# spectrum_8kHz_64Hz.net
KiCad netlist of a schematic drawn in Altium Designer
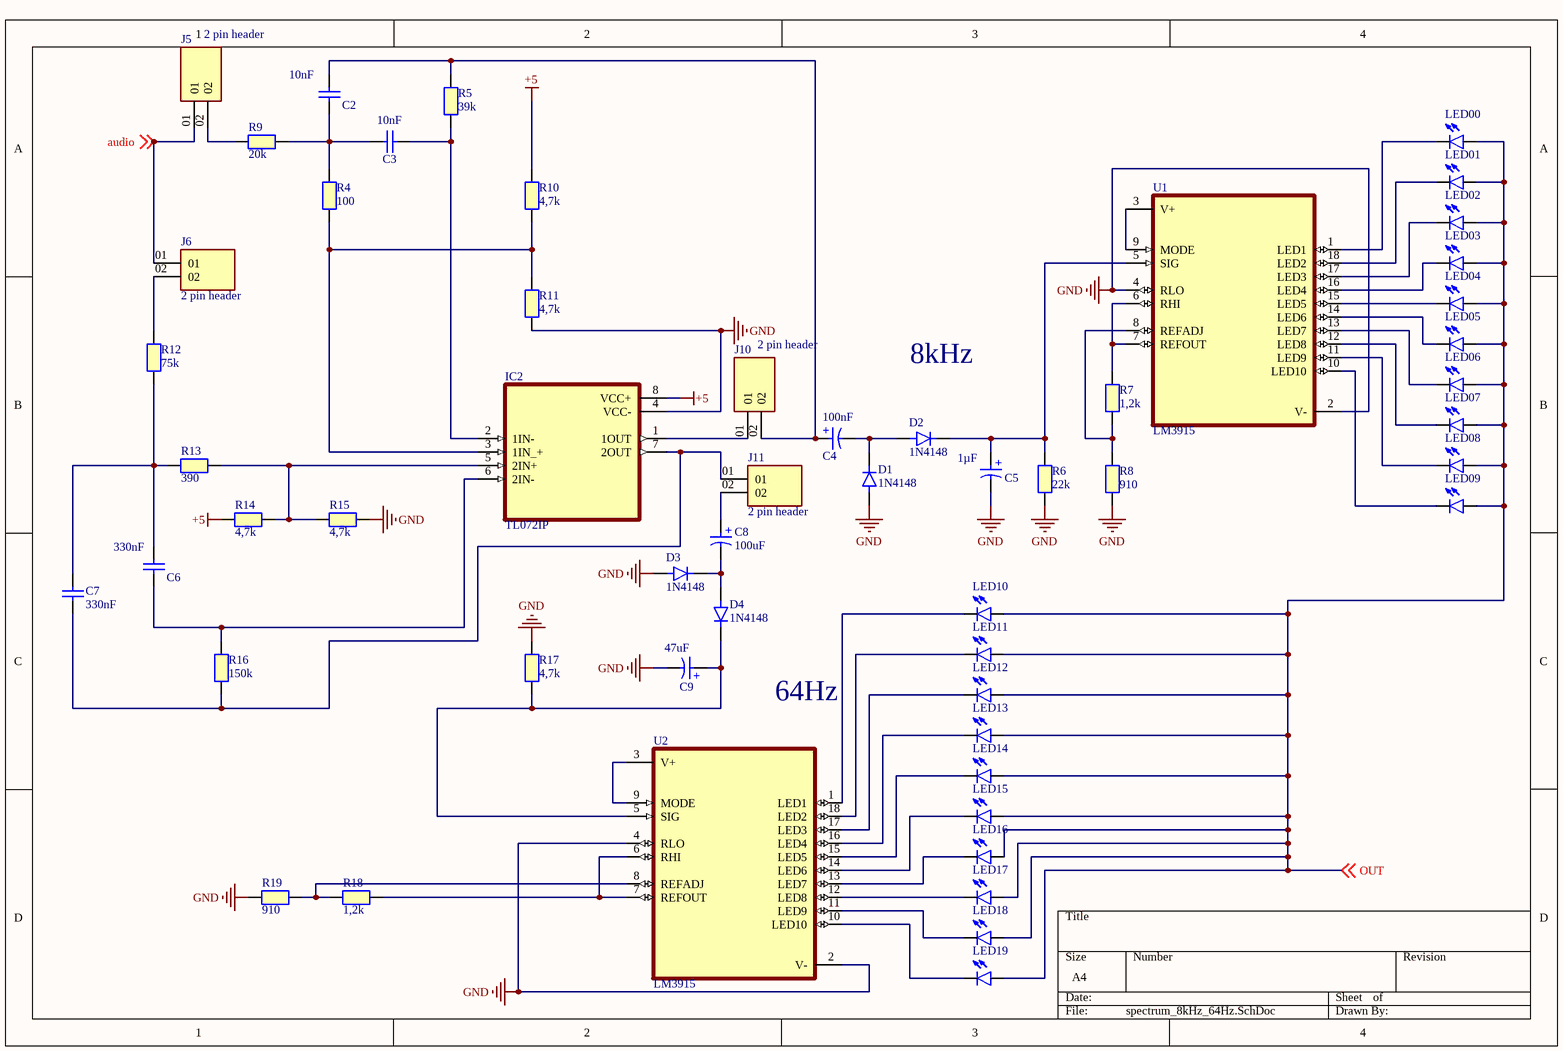
[diagram p0: spectrum_8kHz_64Hz.SchDoc]

(export (version "E")
  (design (tool "Eeschema 10.0.6"))
  (components
    (comp (ref "C2")
      (value "10nF")
      (footprint "CAPC2012X65N")
      (description "10nF ceramic")
      (fields
        (field (name "MANUFACTURER PART NUMBER") "885012004008")
        (field (name "MANUFACTURER") "Wurth Elektronik")
      )
      (libsource (lib "SpectrumComponents") (part "885012004008"))
    )
    (comp (ref "C3")
      (value "10nF")
      (footprint "CAPC2012X65N")
      (description "10nF ceramic")
      (fields
        (field (name "MANUFACTURER PART NUMBER") "885012004008")
        (field (name "MANUFACTURER") "Wurth Elektronik")
      )
      (libsource (lib "SpectrumComponents") (part "885012004008"))
    )
    (comp (ref "C4")
      (value "100nF")
      (footprint "WCAP-ATG8_D5H11")
      (description "Elco 100nF")
      (fields
        (field (name "MANUFACTURER PART NUMBER") "860010272005")
        (field (name "MANUFACTURER") "Wurth Elektronik")
      )
      (libsource (lib "SpectrumComponents") (part "860010272005"))
    )
    (comp (ref "C5")
      (value "1µF")
      (footprint "WCAP-ATG8_D5H11")
      (description "WCAP-ATG8 Aluminum Electrolytic Capacitor, Radial, THT, D5 x H11mm, 1uF, 10V")
      (fields
        (field (name "MANUFACTURER PART NUMBER") "860010272005")
        (field (name "MANUFACTURER") "Wurth Elektronik")
      )
      (libsource (lib "SpectrumComponents") (part "860010272005"))
    )
    (comp (ref "C6")
      (value "330nF")
      (footprint "CAPC2012X65N")
      (description "330nF ceramic")
      (fields
        (field (name "MANUFACTURER PART NUMBER") "885012004008")
        (field (name "MANUFACTURER") "Wurth Elektronik")
      )
      (libsource (lib "SpectrumComponents") (part "885012004008"))
    )
    (comp (ref "C7")
      (value "330nF")
      (footprint "CAPC2012X65N")
      (description "330nF ceramic")
      (fields
        (field (name "MANUFACTURER PART NUMBER") "885012004008")
        (field (name "MANUFACTURER") "Wurth Elektronik")
      )
      (libsource (lib "SpectrumComponents") (part "885012004008"))
    )
    (comp (ref "C8")
      (value "100uF")
      (footprint "WCAP-ATG8_D5H11")
      (description "Elco 100uF")
      (fields
        (field (name "MANUFACTURER PART NUMBER") "860010272005")
        (field (name "MANUFACTURER") "Wurth Elektronik")
      )
      (libsource (lib "SpectrumComponents") (part "860010272005"))
    )
    (comp (ref "C9")
      (value "47uF")
      (footprint "WCAP-ATG8_D5H11")
      (description "WCAP-ATG8 Aluminum Electrolytic Capacitor, Radial, THT, D5 x H11mm, 47µF, 10V")
      (fields
        (field (name "MANUFACTURER PART NUMBER") "860010272005")
        (field (name "MANUFACTURER") "Wurth Elektronik")
      )
      (libsource (lib "SpectrumComponents") (part "860010272005"))
    )
    (comp (ref "D1")
      (value "1N4148")
      (footprint "DIOAD829W49L456D191")
      (description "Diode Standard 75V 200mA Surface Mount SOD-523F")
      (fields (field (name "MF") "ON Semiconductor"))
      (libsource (lib "SpectrumComponents") (part "1N4148"))
    )
    (comp (ref "D2")
      (value "1N4148")
      (footprint "DIOAD829W49L456D191")
      (description "Diode Standard 75V 200mA Surface Mount SOD-523F")
      (fields (field (name "MF") "ON Semiconductor"))
      (libsource (lib "SpectrumComponents") (part "1N4148"))
    )
    (comp (ref "D3")
      (value "1N4148")
      (footprint "DIOAD829W49L456D191")
      (description "Diode Standard 75V 200mA Surface Mount SOD-523F")
      (fields (field (name "MF") "ON Semiconductor"))
      (libsource (lib "SpectrumComponents") (part "1N4148"))
    )
    (comp (ref "D4")
      (value "1N4148")
      (footprint "DIOAD829W49L456D191")
      (description "Diode Standard 75V 200mA Surface Mount SOD-523F")
      (fields (field (name "MF") "ON Semiconductor"))
      (libsource (lib "SpectrumComponents") (part "1N4148"))
    )
    (comp (ref "IC2")
      (value "TL072IP")
      (footprint "DIP794W45P254L959H508Q8")
      (description "Dual, 30-V, 3-MHz, high slew rate (13-V/Âµs), In to V+, JFET-input op amp")
      (fields (field (name "MF") "Texas Instruments"))
      (libsource (lib "SpectrumComponents") (part "TL072IP"))
    )
    (comp (ref "J5")
      (value "2 pin header")
      (footprint "SpectrumComponents:SAMTEC_HTSW-102-07-TM-S")
      (description "2 pin header Jumper")
      (fields (field (name "MP") "HTSW10207TMS") (field (name "MF") "Samtec"))
      (libsource (lib "") (part "2 pin header_1"))
    )
    (comp (ref "J6")
      (value "2 pin header")
      (footprint "SpectrumComponents:SAMTEC_HTSW-102-07-TM-S")
      (description "2 pin header Jumper")
      (fields (field (name "MP") "HTSW10207TMS") (field (name "MF") "Samtec"))
      (libsource (lib "SpectrumComponents") (part "2 pin header"))
    )
    (comp (ref "J10")
      (value "2 pin header")
      (footprint "SpectrumComponents:SAMTEC_HTSW-102-07-TM-S")
      (description "2 pin header Jumper")
      (fields (field (name "MP") "HTSW10207TMS") (field (name "MF") "Samtec"))
      (libsource (lib "") (part "2 pin header_1"))
    )
    (comp (ref "J11")
      (value "2 pin header")
      (footprint "SpectrumComponents:SAMTEC_HTSW-102-07-TM-S")
      (description "2 pin header Jumper")
      (fields (field (name "MP") "HTSW10207TMS") (field (name "MF") "Samtec"))
      (libsource (lib "SpectrumComponents") (part "2 pin header"))
    )
    (comp (ref "LED00")
      (value "LED 2x3x4")
      (footprint "LED 2x3x4mm")
      (description "Green 569nm LED Indication - Discrete 1.9V Radial")
      (fields (field (name "MP") "TLLG4400") (field (name "MF") "Vishay Semiconductors"))
      (libsource (lib "SpectrumComponents") (part "LED 2x3x4"))
    )
    (comp (ref "LED01")
      (value "LED 2x3x4")
      (footprint "LED 2x3x4mm")
      (description "Green 569nm LED Indication - Discrete 1.9V Radial")
      (fields (field (name "MP") "TLLG4400") (field (name "MF") "Vishay Semiconductors"))
      (libsource (lib "SpectrumComponents") (part "LED 2x3x4"))
    )
    (comp (ref "LED02")
      (value "LED 2x3x4")
      (footprint "LED 2x3x4mm")
      (description "Green 569nm LED Indication - Discrete 1.9V Radial")
      (fields (field (name "MP") "TLLG4400") (field (name "MF") "Vishay Semiconductors"))
      (libsource (lib "SpectrumComponents") (part "LED 2x3x4"))
    )
    (comp (ref "LED03")
      (value "LED 2x3x4")
      (footprint "LED 2x3x4mm")
      (description "Green 569nm LED Indication - Discrete 1.9V Radial")
      (fields (field (name "MP") "TLLG4400") (field (name "MF") "Vishay Semiconductors"))
      (libsource (lib "SpectrumComponents") (part "LED 2x3x4"))
    )
    (comp (ref "LED04")
      (value "LED 2x3x4")
      (footprint "LED 2x3x4mm")
      (description "Green 569nm LED Indication - Discrete 1.9V Radial")
      (fields (field (name "MP") "TLLG4400") (field (name "MF") "Vishay Semiconductors"))
      (libsource (lib "SpectrumComponents") (part "LED 2x3x4"))
    )
    (comp (ref "LED05")
      (value "LED 2x3x4")
      (footprint "LED 2x3x4mm")
      (description "Green 569nm LED Indication - Discrete 1.9V Radial")
      (fields (field (name "MP") "TLLG4400") (field (name "MF") "Vishay Semiconductors"))
      (libsource (lib "SpectrumComponents") (part "LED 2x3x4"))
    )
    (comp (ref "LED06")
      (value "LED 2x3x4")
      (footprint "LED 2x3x4mm")
      (description "Green 569nm LED Indication - Discrete 1.9V Radial")
      (fields (field (name "MP") "TLLG4400") (field (name "MF") "Vishay Semiconductors"))
      (libsource (lib "SpectrumComponents") (part "LED 2x3x4"))
    )
    (comp (ref "LED07")
      (value "LED 2x3x4")
      (footprint "LED 2x3x4mm")
      (description "Green 569nm LED Indication - Discrete 1.9V Radial")
      (fields (field (name "MP") "TLLG4400") (field (name "MF") "Vishay Semiconductors"))
      (libsource (lib "SpectrumComponents") (part "LED 2x3x4"))
    )
    (comp (ref "LED08")
      (value "LED 2x3x4")
      (footprint "LED 2x3x4mm")
      (description "Green 569nm LED Indication - Discrete 1.9V Radial")
      (fields (field (name "MP") "TLLG4400") (field (name "MF") "Vishay Semiconductors"))
      (libsource (lib "SpectrumComponents") (part "LED 2x3x4"))
    )
    (comp (ref "LED09")
      (value "LED 2x3x4")
      (footprint "LED 2x3x4mm")
      (description "Green 569nm LED Indication - Discrete 1.9V Radial")
      (fields (field (name "MP") "TLLG4400") (field (name "MF") "Vishay Semiconductors"))
      (libsource (lib "SpectrumComponents") (part "LED 2x3x4"))
    )
    (comp (ref "LED10")
      (value "LED 2x3x4")
      (footprint "LED 2x3x4mm")
      (description "Green 569nm LED Indication - Discrete 1.9V Radial")
      (fields (field (name "MP") "TLLG4400") (field (name "MF") "Vishay Semiconductors"))
      (libsource (lib "SpectrumComponents") (part "LED 2x3x4"))
    )
    (comp (ref "LED11")
      (value "LED 2x3x4")
      (footprint "LED 2x3x4mm")
      (description "Green 569nm LED Indication - Discrete 1.9V Radial")
      (fields (field (name "MP") "TLLG4400") (field (name "MF") "Vishay Semiconductors"))
      (libsource (lib "SpectrumComponents") (part "LED 2x3x4"))
    )
    (comp (ref "LED12")
      (value "LED 2x3x4")
      (footprint "LED 2x3x4mm")
      (description "Green 569nm LED Indication - Discrete 1.9V Radial")
      (fields (field (name "MP") "TLLG4400") (field (name "MF") "Vishay Semiconductors"))
      (libsource (lib "SpectrumComponents") (part "LED 2x3x4"))
    )
    (comp (ref "LED13")
      (value "LED 2x3x4")
      (footprint "LED 2x3x4mm")
      (description "Green 569nm LED Indication - Discrete 1.9V Radial")
      (fields (field (name "MP") "TLLG4400") (field (name "MF") "Vishay Semiconductors"))
      (libsource (lib "SpectrumComponents") (part "LED 2x3x4"))
    )
    (comp (ref "LED14")
      (value "LED 2x3x4")
      (footprint "LED 2x3x4mm")
      (description "Green 569nm LED Indication - Discrete 1.9V Radial")
      (fields (field (name "MP") "TLLG4400") (field (name "MF") "Vishay Semiconductors"))
      (libsource (lib "SpectrumComponents") (part "LED 2x3x4"))
    )
    (comp (ref "LED15")
      (value "LED 2x3x4")
      (footprint "LED 2x3x4mm")
      (description "Green 569nm LED Indication - Discrete 1.9V Radial")
      (fields (field (name "MP") "TLLG4400") (field (name "MF") "Vishay Semiconductors"))
      (libsource (lib "SpectrumComponents") (part "LED 2x3x4"))
    )
    (comp (ref "LED16")
      (value "LED 2x3x4")
      (footprint "LED 2x3x4mm")
      (description "Green 569nm LED Indication - Discrete 1.9V Radial")
      (fields (field (name "MP") "TLLG4400") (field (name "MF") "Vishay Semiconductors"))
      (libsource (lib "SpectrumComponents") (part "LED 2x3x4"))
    )
    (comp (ref "LED17")
      (value "LED 2x3x4")
      (footprint "LED 2x3x4mm")
      (description "Green 569nm LED Indication - Discrete 1.9V Radial")
      (fields (field (name "MP") "TLLG4400") (field (name "MF") "Vishay Semiconductors"))
      (libsource (lib "SpectrumComponents") (part "LED 2x3x4"))
    )
    (comp (ref "LED18")
      (value "LED 2x3x4")
      (footprint "LED 2x3x4mm")
      (description "Green 569nm LED Indication - Discrete 1.9V Radial")
      (fields (field (name "MP") "TLLG4400") (field (name "MF") "Vishay Semiconductors"))
      (libsource (lib "SpectrumComponents") (part "LED 2x3x4"))
    )
    (comp (ref "LED19")
      (value "LED 2x3x4")
      (footprint "LED 2x3x4mm")
      (description "Green 569nm LED Indication - Discrete 1.9V Radial")
      (fields (field (name "MP") "TLLG4400") (field (name "MF") "Vishay Semiconductors"))
      (libsource (lib "SpectrumComponents") (part "LED 2x3x4"))
    )
    (comp (ref "R4")
      (value "100")
      (footprint "RESC2012X50N")
      (description "100Ohm Resistor 0805")
      (fields (field (name "PART NUMBER") "TNPW080510K0BETA") (field (name "MANUFACTURER") "Vishay Dale"))
      (libsource (lib "SpectrumComponents") (part "RESISTOR 0805"))
    )
    (comp (ref "R5")
      (value "39k")
      (footprint "RESC2012X50N")
      (description "4,7k Resistor 0805")
      (fields (field (name "PART NUMBER") "TNPW080510K0BETA") (field (name "MANUFACTURER") "Vishay Dale"))
      (libsource (lib "SpectrumComponents") (part "RESISTOR 0805"))
    )
    (comp (ref "R6")
      (value "22k")
      (footprint "RESC2012X50N")
      (description "22k Resistor 0805")
      (fields (field (name "PART NUMBER") "TNPW080510K0BETA") (field (name "MANUFACTURER") "Vishay Dale"))
      (libsource (lib "SpectrumComponents") (part "RESISTOR 0805"))
    )
    (comp (ref "R7")
      (value "1,2k")
      (footprint "RESC2012X50N")
      (description "1,2k Resistor 0805")
      (fields (field (name "PART NUMBER") "TNPW080510K0BETA") (field (name "MANUFACTURER") "Vishay Dale"))
      (libsource (lib "") (part "RESISTOR 0805_1"))
    )
    (comp (ref "R8")
      (value "910")
      (footprint "RESC2012X50N")
      (description "910 Resistor 0805")
      (fields (field (name "PART NUMBER") "TNPW080510K0BETA") (field (name "MANUFACTURER") "Vishay Dale"))
      (libsource (lib "") (part "RESISTOR 0805_1"))
    )
    (comp (ref "R9")
      (value "20k")
      (footprint "RESC2012X50N")
      (description "20k Resistor 0805")
      (fields (field (name "PART NUMBER") "TNPW080510K0BETA") (field (name "MANUFACTURER") "Vishay Dale"))
      (libsource (lib "") (part "RESISTOR 0805_3"))
    )
    (comp (ref "R10")
      (value "4,7k")
      (footprint "RESC2012X50N")
      (description "4,7k Resistor 0805")
      (fields (field (name "PART NUMBER") "TNPW080510K0BETA") (field (name "MANUFACTURER") "Vishay Dale"))
      (libsource (lib "SpectrumComponents") (part "RESISTOR 0805"))
    )
    (comp (ref "R11")
      (value "4,7k")
      (footprint "RESC2012X50N")
      (description "4,7k Resistor 0805")
      (fields (field (name "PART NUMBER") "TNPW080510K0BETA") (field (name "MANUFACTURER") "Vishay Dale"))
      (libsource (lib "SpectrumComponents") (part "RESISTOR 0805"))
    )
    (comp (ref "R12")
      (value "75k")
      (footprint "RESC2012X50N")
      (description "75k Resistor 0805")
      (fields (field (name "PART NUMBER") "TNPW080510K0BETA") (field (name "MANUFACTURER") "Vishay Dale"))
      (libsource (lib "SpectrumComponents") (part "RESISTOR 0805"))
    )
    (comp (ref "R13")
      (value "390")
      (footprint "RESC2012X50N")
      (description "390 Resistor 0805")
      (fields (field (name "PART NUMBER") "TNPW080510K0BETA") (field (name "MANUFACTURER") "Vishay Dale"))
      (libsource (lib "") (part "RESISTOR 0805_2"))
    )
    (comp (ref "R14")
      (value "4,7k")
      (footprint "RESC2012X50N")
      (description "4,7k Resistor 0805")
      (fields (field (name "PART NUMBER") "TNPW080510K0BETA") (field (name "MANUFACTURER") "Vishay Dale"))
      (libsource (lib "") (part "RESISTOR 0805_2"))
    )
    (comp (ref "R15")
      (value "4,7k")
      (footprint "RESC2012X50N")
      (description "4,7k Resistor 0805")
      (fields (field (name "PART NUMBER") "TNPW080510K0BETA") (field (name "MANUFACTURER") "Vishay Dale"))
      (libsource (lib "") (part "RESISTOR 0805_3"))
    )
    (comp (ref "R16")
      (value "150k")
      (footprint "RESC2012X50N")
      (description "150k Resistor 0805")
      (fields (field (name "PART NUMBER") "TNPW080510K0BETA") (field (name "MANUFACTURER") "Vishay Dale"))
      (libsource (lib "SpectrumComponents") (part "RESISTOR 0805"))
    )
    (comp (ref "R17")
      (value "4,7k")
      (footprint "RESC2012X50N")
      (description "4,7k Resistor 0805")
      (fields (field (name "PART NUMBER") "TNPW080510K0BETA") (field (name "MANUFACTURER") "Vishay Dale"))
      (libsource (lib "") (part "RESISTOR 0805_1"))
    )
    (comp (ref "R18")
      (value "1,2k")
      (footprint "RESC2012X50N")
      (description "1,2k Resistor 0805")
      (fields (field (name "PART NUMBER") "TNPW080510K0BETA") (field (name "MANUFACTURER") "Vishay Dale"))
      (libsource (lib "") (part "RESISTOR 0805_2"))
    )
    (comp (ref "R19")
      (value "910")
      (footprint "RESC2012X50N")
      (description "910 Resistor 0805")
      (fields (field (name "PART NUMBER") "TNPW080510K0BETA") (field (name "MANUFACTURER") "Vishay Dale"))
      (libsource (lib "") (part "RESISTOR 0805_2"))
    )
    (comp (ref "U1")
      (value "LM3915")
      (footprint "SpectrumComponents:DIP952W45P254L2336H533Q18")
      (fields (field (name "MP") "LM3914N-1"))
      (libsource (lib "SpectrumComponents") (part "LM3915"))
    )
    (comp (ref "U2")
      (value "LM3915")
      (footprint "SpectrumComponents:DIP952W45P254L2336H533Q18")
      (fields (field (name "MP") "LM3914N-1"))
      (libsource (lib "SpectrumComponents") (part "LM3915"))
    )
  )
  (nets
    (net (code "1") (name "+5") (class "Default")
      (node (ref "IC2") (pin "8") (pinfunction "VCC+_8") (pintype "power_in"))
      (node (ref "R10") (pin "2") (pinfunction "2_2") (pintype "passive"))
      (node (ref "R14") (pin "2") (pinfunction "2_2") (pintype "passive"))
    )
    (net (code "2") (name "GND") (class "Default")
      (node (ref "C5") (pin "2") (pinfunction "N_2") (pintype "passive"))
      (node (ref "C9") (pin "2") (pinfunction "N_2") (pintype "passive"))
      (node (ref "D1") (pin "A") (pinfunction "A_A") (pintype "passive"))
      (node (ref "D3") (pin "A") (pinfunction "A_A") (pintype "passive"))
      (node (ref "IC2") (pin "4") (pinfunction "VCC-_4") (pintype "power_in"))
      (node (ref "R11") (pin "1") (pinfunction "1_1") (pintype "passive"))
      (node (ref "R15") (pin "2") (pinfunction "2_2") (pintype "passive"))
      (node (ref "R17") (pin "1") (pinfunction "1_1") (pintype "passive"))
      (node (ref "R19") (pin "2") (pinfunction "2_2") (pintype "passive"))
      (node (ref "R6") (pin "1") (pinfunction "1_1") (pintype "passive"))
      (node (ref "R8") (pin "2") (pinfunction "2_2") (pintype "passive"))
      (node (ref "U1") (pin "2") (pinfunction "V-_2") (pintype "power_in"))
      (node (ref "U1") (pin "4") (pinfunction "RLO_4") (pintype "bidirectional"))
      (node (ref "U2") (pin "2") (pinfunction "V-_2") (pintype "power_in"))
      (node (ref "U2") (pin "4") (pinfunction "RLO_4") (pintype "bidirectional"))
    )
    (net (code "3") (name "Net-(C2-Pad1)") (class "Default")
      (node (ref "C2") (pin "1") (pinfunction "1_1") (pintype "passive"))
      (node (ref "C3") (pin "1") (pinfunction "1_1") (pintype "passive"))
      (node (ref "R4") (pin "2") (pinfunction "2_2") (pintype "passive"))
      (node (ref "R9") (pin "2") (pinfunction "2_2") (pintype "passive"))
    )
    (net (code "4") (name "Net-(C4-N)") (class "Default")
      (node (ref "C4") (pin "2") (pinfunction "N_2") (pintype "passive"))
      (node (ref "D1") (pin "C") (pinfunction "C_C") (pintype "passive"))
      (node (ref "D2") (pin "A") (pinfunction "A_A") (pintype "passive"))
    )
    (net (code "5") (name "Net-(C4-P)") (class "Default")
      (node (ref "C2") (pin "2") (pinfunction "2_2") (pintype "passive"))
      (node (ref "C4") (pin "1") (pinfunction "P_1") (pintype "passive"))
      (node (ref "J10") (pin "02") (pinfunction "02_02") (pintype "passive"))
      (node (ref "R5") (pin "2") (pinfunction "2_2") (pintype "passive"))
    )
    (net (code "6") (name "Net-(C5-P)") (class "Default")
      (node (ref "C5") (pin "1") (pinfunction "P_1") (pintype "passive"))
      (node (ref "D2") (pin "C") (pinfunction "C_C") (pintype "passive"))
      (node (ref "R6") (pin "2") (pinfunction "2_2") (pintype "passive"))
      (node (ref "U1") (pin "5") (pinfunction "SIG_5") (pintype "input"))
    )
    (net (code "7") (name "Net-(C6-Pad2)") (class "Default")
      (node (ref "C6") (pin "2") (pinfunction "2_2") (pintype "passive"))
      (node (ref "C7") (pin "2") (pinfunction "2_2") (pintype "passive"))
      (node (ref "R12") (pin "1") (pinfunction "1_1") (pintype "passive"))
      (node (ref "R13") (pin "2") (pinfunction "2_2") (pintype "passive"))
    )
    (net (code "8") (name "Net-(C8-N)") (class "Default")
      (node (ref "C8") (pin "2") (pinfunction "N_2") (pintype "passive"))
      (node (ref "D3") (pin "C") (pinfunction "C_C") (pintype "passive"))
      (node (ref "D4") (pin "A") (pinfunction "A_A") (pintype "passive"))
    )
    (net (code "9") (name "Net-(C8-P)") (class "Default")
      (node (ref "C8") (pin "1") (pinfunction "P_1") (pintype "passive"))
      (node (ref "J11") (pin "02") (pinfunction "02_02") (pintype "passive"))
    )
    (net (code "10") (name "Net-(C9-P)") (class "Default")
      (node (ref "C9") (pin "1") (pinfunction "P_1") (pintype "passive"))
      (node (ref "D4") (pin "C") (pinfunction "C_C") (pintype "passive"))
      (node (ref "R17") (pin "2") (pinfunction "2_2") (pintype "passive"))
      (node (ref "U2") (pin "5") (pinfunction "SIG_5") (pintype "input"))
    )
    (net (code "11") (name "Net-(IC2-1IN-)") (class "Default")
      (node (ref "C3") (pin "2") (pinfunction "2_2") (pintype "passive"))
      (node (ref "IC2") (pin "2") (pinfunction "1IN-_2") (pintype "input"))
      (node (ref "R5") (pin "1") (pinfunction "1_1") (pintype "passive"))
    )
    (net (code "12") (name "Net-(IC2-1IN_+)") (class "Default")
      (node (ref "IC2") (pin "3") (pinfunction "1IN_+_3") (pintype "input"))
      (node (ref "R10") (pin "1") (pinfunction "1_1") (pintype "passive"))
      (node (ref "R11") (pin "2") (pinfunction "2_2") (pintype "passive"))
      (node (ref "R4") (pin "1") (pinfunction "1_1") (pintype "passive"))
    )
    (net (code "13") (name "Net-(IC2-1OUT)") (class "Default")
      (node (ref "IC2") (pin "1") (pinfunction "1OUT_1") (pintype "output"))
      (node (ref "J10") (pin "01") (pinfunction "01_01") (pintype "passive"))
    )
    (net (code "14") (name "Net-(IC2-2IN+)") (class "Default")
      (node (ref "IC2") (pin "5") (pinfunction "2IN+_5") (pintype "input"))
      (node (ref "R13") (pin "1") (pinfunction "1_1") (pintype "passive"))
      (node (ref "R14") (pin "1") (pinfunction "1_1") (pintype "passive"))
      (node (ref "R15") (pin "1") (pinfunction "1_1") (pintype "passive"))
    )
    (net (code "15") (name "Net-(IC2-2IN-)") (class "Default")
      (node (ref "C6") (pin "1") (pinfunction "1_1") (pintype "passive"))
      (node (ref "IC2") (pin "6") (pinfunction "2IN-_6") (pintype "input"))
      (node (ref "R16") (pin "2") (pinfunction "2_2") (pintype "passive"))
    )
    (net (code "16") (name "Net-(IC2-2OUT)") (class "Default")
      (node (ref "C7") (pin "1") (pinfunction "1_1") (pintype "passive"))
      (node (ref "IC2") (pin "7") (pinfunction "2OUT_7") (pintype "output"))
      (node (ref "J11") (pin "01") (pinfunction "01_01") (pintype "passive"))
      (node (ref "R16") (pin "1") (pinfunction "1_1") (pintype "passive"))
    )
    (net (code "17") (name "Net-(J5-Pad02)") (class "Default")
      (node (ref "J5") (pin "02") (pinfunction "02_02") (pintype "passive"))
      (node (ref "R9") (pin "1") (pinfunction "1_1") (pintype "passive"))
    )
    (net (code "18") (name "Net-(J6-Pad02)") (class "Default")
      (node (ref "J6") (pin "02") (pinfunction "02_02") (pintype "passive"))
      (node (ref "R12") (pin "2") (pinfunction "2_2") (pintype "passive"))
    )
    (net (code "19") (name "Net-(LED00-C)") (class "Default")
      (node (ref "LED00") (pin "K") (pinfunction "C_K") (pintype "passive"))
      (node (ref "U1") (pin "1") (pinfunction "LED1_1") (pintype "bidirectional"))
    )
    (net (code "20") (name "Net-(LED01-C)") (class "Default")
      (node (ref "LED01") (pin "K") (pinfunction "C_K") (pintype "passive"))
      (node (ref "U1") (pin "18") (pinfunction "LED2_18") (pintype "bidirectional"))
    )
    (net (code "21") (name "Net-(LED02-C)") (class "Default")
      (node (ref "LED02") (pin "K") (pinfunction "C_K") (pintype "passive"))
      (node (ref "U1") (pin "17") (pinfunction "LED3_17") (pintype "bidirectional"))
    )
    (net (code "22") (name "Net-(LED03-C)") (class "Default")
      (node (ref "LED03") (pin "K") (pinfunction "C_K") (pintype "passive"))
      (node (ref "U1") (pin "16") (pinfunction "LED4_16") (pintype "bidirectional"))
    )
    (net (code "23") (name "Net-(LED04-C)") (class "Default")
      (node (ref "LED04") (pin "K") (pinfunction "C_K") (pintype "passive"))
      (node (ref "U1") (pin "15") (pinfunction "LED5_15") (pintype "bidirectional"))
    )
    (net (code "24") (name "Net-(LED05-C)") (class "Default")
      (node (ref "LED05") (pin "K") (pinfunction "C_K") (pintype "passive"))
      (node (ref "U1") (pin "14") (pinfunction "LED6_14") (pintype "bidirectional"))
    )
    (net (code "25") (name "Net-(LED06-C)") (class "Default")
      (node (ref "LED06") (pin "K") (pinfunction "C_K") (pintype "passive"))
      (node (ref "U1") (pin "13") (pinfunction "LED7_13") (pintype "bidirectional"))
    )
    (net (code "26") (name "Net-(LED07-C)") (class "Default")
      (node (ref "LED07") (pin "K") (pinfunction "C_K") (pintype "passive"))
      (node (ref "U1") (pin "12") (pinfunction "LED8_12") (pintype "bidirectional"))
    )
    (net (code "27") (name "Net-(LED08-C)") (class "Default")
      (node (ref "LED08") (pin "K") (pinfunction "C_K") (pintype "passive"))
      (node (ref "U1") (pin "11") (pinfunction "LED9_11") (pintype "bidirectional"))
    )
    (net (code "28") (name "Net-(LED09-C)") (class "Default")
      (node (ref "LED09") (pin "K") (pinfunction "C_K") (pintype "passive"))
      (node (ref "U1") (pin "10") (pinfunction "LED10_10") (pintype "bidirectional"))
    )
    (net (code "29") (name "Net-(LED10-C)") (class "Default")
      (node (ref "LED10") (pin "K") (pinfunction "C_K") (pintype "passive"))
      (node (ref "U2") (pin "1") (pinfunction "LED1_1") (pintype "bidirectional"))
    )
    (net (code "30") (name "Net-(LED11-C)") (class "Default")
      (node (ref "LED11") (pin "K") (pinfunction "C_K") (pintype "passive"))
      (node (ref "U2") (pin "18") (pinfunction "LED2_18") (pintype "bidirectional"))
    )
    (net (code "31") (name "Net-(LED12-C)") (class "Default")
      (node (ref "LED12") (pin "K") (pinfunction "C_K") (pintype "passive"))
      (node (ref "U2") (pin "17") (pinfunction "LED3_17") (pintype "bidirectional"))
    )
    (net (code "32") (name "Net-(LED13-C)") (class "Default")
      (node (ref "LED13") (pin "K") (pinfunction "C_K") (pintype "passive"))
      (node (ref "U2") (pin "16") (pinfunction "LED4_16") (pintype "bidirectional"))
    )
    (net (code "33") (name "Net-(LED14-C)") (class "Default")
      (node (ref "LED14") (pin "K") (pinfunction "C_K") (pintype "passive"))
      (node (ref "U2") (pin "15") (pinfunction "LED5_15") (pintype "bidirectional"))
    )
    (net (code "34") (name "Net-(LED15-C)") (class "Default")
      (node (ref "LED15") (pin "K") (pinfunction "C_K") (pintype "passive"))
      (node (ref "U2") (pin "14") (pinfunction "LED6_14") (pintype "bidirectional"))
    )
    (net (code "35") (name "Net-(LED16-C)") (class "Default")
      (node (ref "LED16") (pin "K") (pinfunction "C_K") (pintype "passive"))
      (node (ref "U2") (pin "13") (pinfunction "LED7_13") (pintype "bidirectional"))
    )
    (net (code "36") (name "Net-(LED17-C)") (class "Default")
      (node (ref "LED17") (pin "K") (pinfunction "C_K") (pintype "passive"))
      (node (ref "U2") (pin "12") (pinfunction "LED8_12") (pintype "bidirectional"))
    )
    (net (code "37") (name "Net-(LED18-C)") (class "Default")
      (node (ref "LED18") (pin "K") (pinfunction "C_K") (pintype "passive"))
      (node (ref "U2") (pin "11") (pinfunction "LED9_11") (pintype "bidirectional"))
    )
    (net (code "38") (name "Net-(LED19-C)") (class "Default")
      (node (ref "LED19") (pin "K") (pinfunction "C_K") (pintype "passive"))
      (node (ref "U2") (pin "10") (pinfunction "LED10_10") (pintype "bidirectional"))
    )
    (net (code "39") (name "Net-(U1-MODE)") (class "Default")
      (node (ref "U1") (pin "3") (pinfunction "V+_3") (pintype "power_in"))
      (node (ref "U1") (pin "9") (pinfunction "MODE_9") (pintype "input"))
    )
    (net (code "40") (name "Net-(U1-REFADJ)") (class "Default")
      (node (ref "R7") (pin "2") (pinfunction "2_2") (pintype "passive"))
      (node (ref "R8") (pin "1") (pinfunction "1_1") (pintype "passive"))
      (node (ref "U1") (pin "8") (pinfunction "REFADJ_8") (pintype "bidirectional"))
    )
    (net (code "41") (name "Net-(U1-REFOUT)") (class "Default")
      (node (ref "R7") (pin "1") (pinfunction "1_1") (pintype "passive"))
      (node (ref "U1") (pin "6") (pinfunction "RHI_6") (pintype "bidirectional"))
      (node (ref "U1") (pin "7") (pinfunction "REFOUT_7") (pintype "bidirectional"))
    )
    (net (code "42") (name "Net-(U2-MODE)") (class "Default")
      (node (ref "U2") (pin "3") (pinfunction "V+_3") (pintype "power_in"))
      (node (ref "U2") (pin "9") (pinfunction "MODE_9") (pintype "input"))
    )
    (net (code "43") (name "Net-(U2-REFADJ)") (class "Default")
      (node (ref "R18") (pin "2") (pinfunction "2_2") (pintype "passive"))
      (node (ref "R19") (pin "1") (pinfunction "1_1") (pintype "passive"))
      (node (ref "U2") (pin "8") (pinfunction "REFADJ_8") (pintype "bidirectional"))
    )
    (net (code "44") (name "Net-(U2-REFOUT)") (class "Default")
      (node (ref "R18") (pin "1") (pinfunction "1_1") (pintype "passive"))
      (node (ref "U2") (pin "6") (pinfunction "RHI_6") (pintype "bidirectional"))
      (node (ref "U2") (pin "7") (pinfunction "REFOUT_7") (pintype "bidirectional"))
    )
    (net (code "45") (name "OUT") (class "Default")
      (node (ref "LED00") (pin "A") (pinfunction "A_A") (pintype "passive"))
      (node (ref "LED01") (pin "A") (pinfunction "A_A") (pintype "passive"))
      (node (ref "LED02") (pin "A") (pinfunction "A_A") (pintype "passive"))
      (node (ref "LED03") (pin "A") (pinfunction "A_A") (pintype "passive"))
      (node (ref "LED04") (pin "A") (pinfunction "A_A") (pintype "passive"))
      (node (ref "LED05") (pin "A") (pinfunction "A_A") (pintype "passive"))
      (node (ref "LED06") (pin "A") (pinfunction "A_A") (pintype "passive"))
      (node (ref "LED07") (pin "A") (pinfunction "A_A") (pintype "passive"))
      (node (ref "LED08") (pin "A") (pinfunction "A_A") (pintype "passive"))
      (node (ref "LED09") (pin "A") (pinfunction "A_A") (pintype "passive"))
      (node (ref "LED10") (pin "A") (pinfunction "A_A") (pintype "passive"))
      (node (ref "LED11") (pin "A") (pinfunction "A_A") (pintype "passive"))
      (node (ref "LED12") (pin "A") (pinfunction "A_A") (pintype "passive"))
      (node (ref "LED13") (pin "A") (pinfunction "A_A") (pintype "passive"))
      (node (ref "LED14") (pin "A") (pinfunction "A_A") (pintype "passive"))
      (node (ref "LED15") (pin "A") (pinfunction "A_A") (pintype "passive"))
      (node (ref "LED16") (pin "A") (pinfunction "A_A") (pintype "passive"))
      (node (ref "LED17") (pin "A") (pinfunction "A_A") (pintype "passive"))
      (node (ref "LED18") (pin "A") (pinfunction "A_A") (pintype "passive"))
      (node (ref "LED19") (pin "A") (pinfunction "A_A") (pintype "passive"))
    )
    (net (code "46") (name "audio") (class "Default")
      (node (ref "J5") (pin "01") (pinfunction "01_01") (pintype "passive"))
      (node (ref "J6") (pin "01") (pinfunction "01_01") (pintype "passive"))
    )
  )
)
